# generator.net
KiCad netlist of a schematic drawn in EAGLE
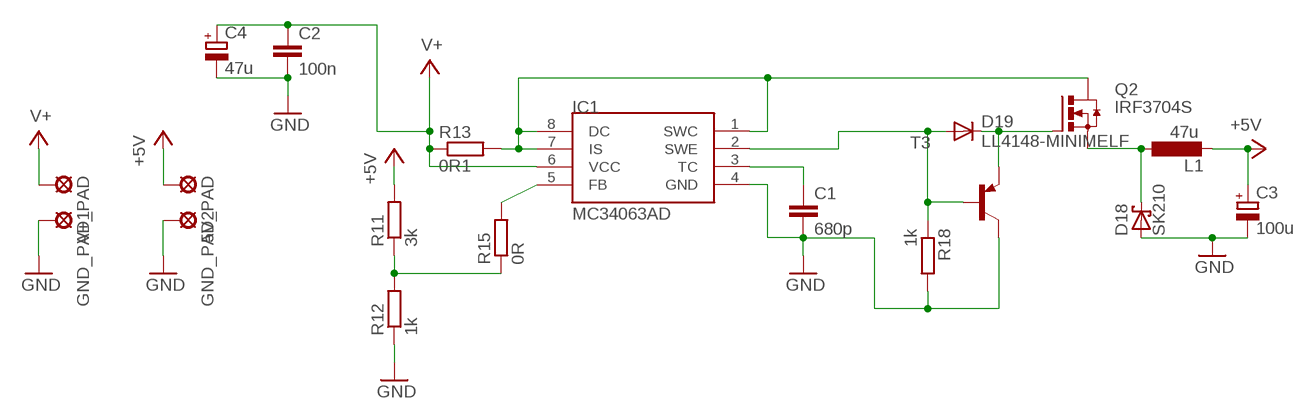
[diagram p0: schematic, sheet 1]

(export (version "E")
  (design (tool "Eeschema 10.0.6"))
  (components
    (comp (ref "5V_PAD")
      (value "LSP10")
      (footprint "eagle-import:LSP10")
      (libsource (lib "eagle-import") (part "LSP10"))
    )
    (comp (ref "C1")
      (value "680p")
      (footprint "eagle-import:C0805")
      (libsource (lib "eagle-import") (part "C-EUC0805"))
    )
    (comp (ref "C2")
      (value "100n")
      (footprint "eagle-import:C0805")
      (libsource (lib "eagle-import") (part "C-EUC0805"))
    )
    (comp (ref "C3")
      (value "100u")
      (footprint "eagle-import:PANASONIC_D")
      (libsource (lib "eagle-import") (part "CPOL-EUD"))
    )
    (comp (ref "C4")
      (value "47u")
      (footprint "eagle-import:E3,5-10")
      (libsource (lib "eagle-import") (part "CPOL-EUE3.5-10"))
    )
    (comp (ref "D18")
      (value "SK210")
      (footprint "eagle-import:SMB")
      (libsource (lib "eagle-import") (part "SCHOTTKY-DIODESMD"))
    )
    (comp (ref "D19")
      (value "LL4148-MINIMELF")
      (footprint "eagle-import:SOD80C")
      (libsource (lib "eagle-import") (part "PMLL41SOD80C"))
    )
    (comp (ref "GND_PAD1")
      (value "LSP10")
      (footprint "eagle-import:LSP10")
      (libsource (lib "eagle-import") (part "LSP10"))
    )
    (comp (ref "GND_PAD2")
      (value "LSP10")
      (footprint "eagle-import:LSP10")
      (libsource (lib "eagle-import") (part "LSP10"))
    )
    (comp (ref "IC1")
      (value "MC34063AD")
      (footprint "eagle-import:SOIC8")
      (libsource (lib "eagle-import") (part "MC34063AD"))
    )
    (comp (ref "L1")
      (value "47u")
      (footprint "eagle-import:TJ3-U1")
      (libsource (lib "eagle-import") (part "L-EUTJ3-U1"))
    )
    (comp (ref "Q2")
      (value "IRF3704S")
      (footprint "eagle-import:D2PACK")
      (libsource (lib "eagle-import") (part "IRF3704S"))
    )
    (comp (ref "R11")
      (value "3k")
      (footprint "eagle-import:R0805")
      (libsource (lib "eagle-import") (part "R-EU_R0805"))
    )
    (comp (ref "R12")
      (value "1k")
      (footprint "eagle-import:R0805")
      (libsource (lib "eagle-import") (part "R-EU_R0805"))
    )
    (comp (ref "R13")
      (value "0R1")
      (footprint "eagle-import:R0805")
      (libsource (lib "eagle-import") (part "R-EU_R0805"))
    )
    (comp (ref "R15")
      (value "0R")
      (footprint "eagle-import:R1206")
      (libsource (lib "eagle-import") (part "R-EU_R1206"))
    )
    (comp (ref "R18")
      (value "1k")
      (footprint "eagle-import:R0805")
      (libsource (lib "eagle-import") (part "resistor_R-EU_R0805"))
    )
    (comp (ref "T3")
      (value "BC807-16-PNP-SOT23-BEC")
      (footprint "eagle-import:SOT23-BEC")
      (libsource (lib "eagle-import") (part "-PNP-SOT23-BECBC807-16"))
    )
    (comp (ref "V+_PAD")
      (value "LSP10")
      (footprint "eagle-import:LSP10")
      (libsource (lib "eagle-import") (part "LSP10"))
    )
  )
  (nets
    (net (code "1") (name "+5V") (class "Default")
      (node (ref "5V_PAD") (pin "MP") (pinfunction "MP_MP") (pintype "passive"))
      (node (ref "C3") (pin "+") (pinfunction "+_+") (pintype "passive"))
      (node (ref "L1") (pin "2") (pinfunction "2_2") (pintype "passive"))
      (node (ref "R11") (pin "2") (pinfunction "2_2") (pintype "passive"))
    )
    (net (code "2") (name "GND") (class "Default")
      (node (ref "C1") (pin "2") (pinfunction "2_2") (pintype "passive"))
      (node (ref "C2") (pin "2") (pinfunction "2_2") (pintype "passive"))
      (node (ref "C3") (pin "-") (pinfunction "-_-") (pintype "passive"))
      (node (ref "C4") (pin "-") (pinfunction "-_-") (pintype "passive"))
      (node (ref "D18") (pin "A") (pinfunction "A_A") (pintype "passive"))
      (node (ref "GND_PAD1") (pin "MP") (pinfunction "MP_MP") (pintype "passive"))
      (node (ref "GND_PAD2") (pin "MP") (pinfunction "MP_MP") (pintype "passive"))
      (node (ref "IC1") (pin "4") (pinfunction "GND_4") (pintype "passive"))
      (node (ref "R12") (pin "1") (pinfunction "1_1") (pintype "passive"))
      (node (ref "R18") (pin "2") (pinfunction "2_2") (pintype "passive"))
      (node (ref "T3") (pin "C") (pinfunction "C_C") (pintype "passive"))
    )
    (net (code "3") (name "Net-(IC1-DC)") (class "Default")
      (node (ref "IC1") (pin "1") (pinfunction "SWC_1") (pintype "passive"))
      (node (ref "IC1") (pin "7") (pinfunction "IS_7") (pintype "passive"))
      (node (ref "IC1") (pin "8") (pinfunction "DC_8") (pintype "passive"))
      (node (ref "Q2") (pin "2") (pinfunction "D_2") (pintype "passive"))
      (node (ref "R13") (pin "2") (pinfunction "2_2") (pintype "passive"))
    )
    (net (code "4") (name "Net-(IC1-FB)") (class "Default")
      (node (ref "IC1") (pin "5") (pinfunction "FB_5") (pintype "passive"))
      (node (ref "R15") (pin "2") (pinfunction "2_2") (pintype "passive"))
    )
    (net (code "5") (name "Net-(IC1-SWE)") (class "Default")
      (node (ref "D19") (pin "A") (pinfunction "A_A") (pintype "passive"))
      (node (ref "IC1") (pin "2") (pinfunction "SWE_2") (pintype "passive"))
      (node (ref "R18") (pin "1") (pinfunction "1_1") (pintype "passive"))
      (node (ref "T3") (pin "B") (pinfunction "B_B") (pintype "passive"))
    )
    (net (code "6") (name "Net-(IC1-TC)") (class "Default")
      (node (ref "C1") (pin "1") (pinfunction "1_1") (pintype "passive"))
      (node (ref "IC1") (pin "3") (pinfunction "TC_3") (pintype "passive"))
    )
    (net (code "7") (name "Net-(Q2-G)") (class "Default")
      (node (ref "D19") (pin "C") (pinfunction "C_C") (pintype "passive"))
      (node (ref "Q2") (pin "1") (pinfunction "G_1") (pintype "passive"))
      (node (ref "T3") (pin "E") (pinfunction "E_E") (pintype "passive"))
    )
    (net (code "8") (name "Net-(Q2-S)") (class "Default")
      (node (ref "D18") (pin "C") (pinfunction "C_C") (pintype "passive"))
      (node (ref "L1") (pin "1") (pinfunction "1_1") (pintype "passive"))
      (node (ref "Q2") (pin "3") (pinfunction "S_3") (pintype "passive"))
    )
    (net (code "9") (name "Net-(R11-Pad1)") (class "Default")
      (node (ref "R11") (pin "1") (pinfunction "1_1") (pintype "passive"))
      (node (ref "R12") (pin "2") (pinfunction "2_2") (pintype "passive"))
      (node (ref "R15") (pin "1") (pinfunction "1_1") (pintype "passive"))
    )
    (net (code "10") (name "V+") (class "Default")
      (node (ref "C2") (pin "1") (pinfunction "1_1") (pintype "passive"))
      (node (ref "C4") (pin "+") (pinfunction "+_+") (pintype "passive"))
      (node (ref "IC1") (pin "6") (pinfunction "VCC_6") (pintype "passive"))
      (node (ref "R13") (pin "1") (pinfunction "1_1") (pintype "passive"))
      (node (ref "V+_PAD") (pin "MP") (pinfunction "MP_MP") (pintype "passive"))
    )
  )
)
